# TopLevelDesign.net
KiCad netlist of a schematic drawn in Altium Designer
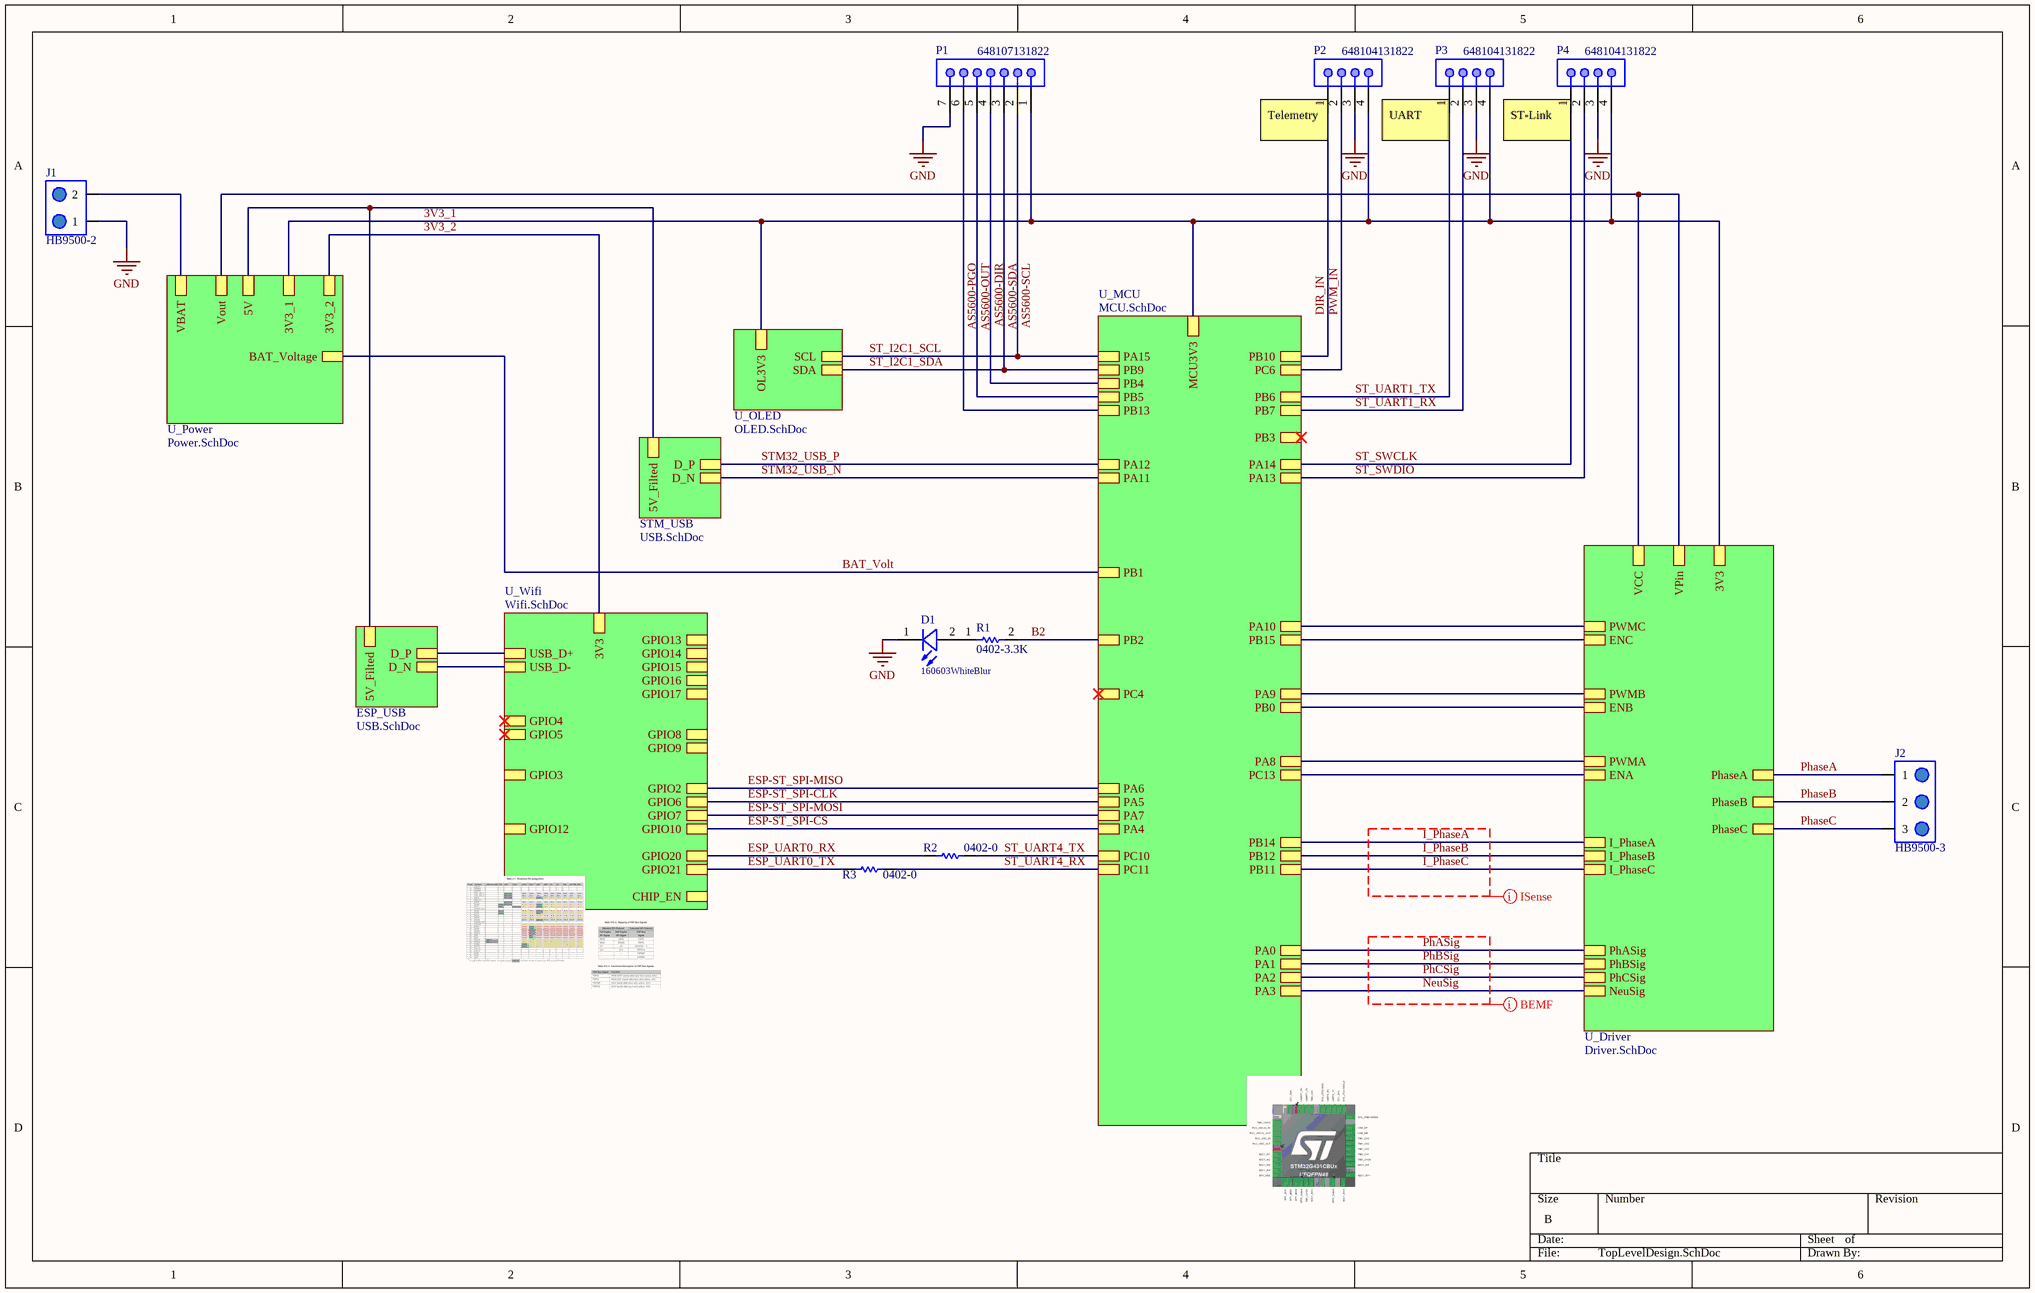
[diagram p0: TopLevelDesign.SchDoc]

(export (version "E")
  (design (tool "Eeschema 10.0.6"))
  (components
    (comp (ref "D1")
      (value "160603WhiteBlur")
      (footprint "WL-SMCW_0603_H=0.7mm")
      (description "WL-SMCW SMT Mono-color Chip LED Blur, size 0603, White")
      (libsource (lib "Tin Tran") (part "160603WhiteClear"))
    )
    (comp (ref "J1")
      (value "HB9500-2")
      (footprint "HB9500-2")
      (description "High Power Terminal , 25A , 300V")
      (libsource (lib "Tin Tran") (part "HB9500-2"))
    )
    (comp (ref "J2")
      (value "HB9500-3")
      (footprint "HB9500-3")
      (description "High Power Terminal , 25A , 300V")
      (libsource (lib "Tin Tran") (part "HB9500-3"))
    )
    (comp (ref "P1")
      (value "648107131822")
      (footprint "648107131822")
      (description "WR-WTB SMT Male Horizontal Shrouded Header, pitch 1.5mm, 7p")
      (fields (field (name "PUBLISHER") "Wurth Elektronik"))
      (libsource (lib "Tin Tran") (part "679307124022"))
    )
    (comp (ref "P2")
      (value "648104131822")
      (footprint "648104131822")
      (description "WR-WTB SMT Male Horizontal Shrouded Header, pitch 1.5mm, 4p")
      (fields (field (name "PUBLISHER") "Wurth Elektronik"))
      (libsource (lib "Tin Tran") (part "679304124022"))
    )
    (comp (ref "P3")
      (value "648104131822")
      (footprint "648104131822")
      (description "WR-WTB SMT Male Horizontal Shrouded Header, pitch 1.5mm, 4p")
      (fields (field (name "PUBLISHER") "Wurth Elektronik"))
      (libsource (lib "Tin Tran") (part "679304124022"))
    )
    (comp (ref "P4")
      (value "648104131822")
      (footprint "648104131822")
      (description "WR-WTB SMT Male Horizontal Shrouded Header, pitch 1.5mm, 4p")
      (fields (field (name "PUBLISHER") "Wurth Elektronik"))
      (libsource (lib "Tin Tran") (part "679304124022"))
    )
    (comp (ref "R1")
      (value "0402-3.3K")
      (footprint "R-0402-10K")
      (description "RES 0402 3.3K")
      (libsource (lib "") (part "0402_1"))
    )
    (comp (ref "R2")
      (value "0402-0")
      (footprint "R-0402-1K")
      (description "0402Resistor 0 Ohm")
      (libsource (lib "Tin Tran") (part "0402"))
    )
    (comp (ref "R3")
      (value "0402-0")
      (footprint "R-0402-1K")
      (description "0402Resistor 0 Ohm")
      (libsource (lib "Tin Tran") (part "0402"))
    )
  )
  (nets
    (net (code "1") (name "/3V3_1") (class "Default")
      (node (ref "P1") (pin "1") (pinfunction "1_1") (pintype "passive"))
      (node (ref "P2") (pin "4") (pinfunction "4_4") (pintype "passive"))
      (node (ref "P3") (pin "4") (pinfunction "4_4") (pintype "passive"))
      (node (ref "P4") (pin "4") (pinfunction "4_4") (pintype "passive"))
    )
    (net (code "4") (name "/AS5600-DIR") (class "Default")
      (node (ref "P1") (pin "4") (pinfunction "4_4") (pintype "passive"))
    )
    (net (code "5") (name "/AS5600-OUT") (class "Default")
      (node (ref "P1") (pin "5") (pinfunction "5_5") (pintype "passive"))
    )
    (net (code "6") (name "/AS5600-PGO") (class "Default")
      (node (ref "P1") (pin "6") (pinfunction "6_6") (pintype "passive"))
    )
    (net (code "7") (name "/AS5600-SCL") (class "Default")
      (node (ref "P1") (pin "2") (pinfunction "2_2") (pintype "passive"))
    )
    (net (code "8") (name "/AS5600-SDA") (class "Default")
      (node (ref "P1") (pin "3") (pinfunction "3_3") (pintype "passive"))
    )
    (net (code "9") (name "/B2") (class "Default")
      (node (ref "R1") (pin "2") (pinfunction "2_2") (pintype "passive"))
    )
    (net (code "12") (name "/DIR_IN") (class "Default")
      (node (ref "P2") (pin "1") (pinfunction "1_1") (pintype "passive"))
    )
    (net (code "22") (name "/ESP_UART0_RX") (class "Default")
      (node (ref "R2") (pin "1") (pinfunction "1_1") (pintype "passive"))
    )
    (net (code "23") (name "/ESP_UART0_TX") (class "Default")
      (node (ref "R3") (pin "1") (pinfunction "1_1") (pintype "passive"))
    )
    (net (code "44") (name "/PWM_IN") (class "Default")
      (node (ref "P2") (pin "2") (pinfunction "2_2") (pintype "passive"))
    )
    (net (code "48") (name "/PhaseA") (class "Default")
      (node (ref "J2") (pin "1") (pinfunction "1_1") (pintype "passive"))
    )
    (net (code "49") (name "/PhaseB") (class "Default")
      (node (ref "J2") (pin "2") (pinfunction "2_2") (pintype "passive"))
    )
    (net (code "50") (name "/PhaseC") (class "Default")
      (node (ref "J2") (pin "3") (pinfunction "3_3") (pintype "passive"))
    )
    (net (code "53") (name "/ST_SWCLK") (class "Default")
      (node (ref "P4") (pin "1") (pinfunction "1_1") (pintype "passive"))
    )
    (net (code "54") (name "/ST_SWDIO") (class "Default")
      (node (ref "P4") (pin "2") (pinfunction "2_2") (pintype "passive"))
    )
    (net (code "55") (name "/ST_UART1_RX") (class "Default")
      (node (ref "P3") (pin "2") (pinfunction "2_2") (pintype "passive"))
    )
    (net (code "56") (name "/ST_UART1_TX") (class "Default")
      (node (ref "P3") (pin "1") (pinfunction "1_1") (pintype "passive"))
    )
    (net (code "57") (name "/ST_UART4_RX") (class "Default")
      (node (ref "R3") (pin "2") (pinfunction "2_2") (pintype "passive"))
    )
    (net (code "58") (name "/ST_UART4_TX") (class "Default")
      (node (ref "R2") (pin "2") (pinfunction "2_2") (pintype "passive"))
    )
    (net (code "59") (name "/VBAT") (class "Default")
      (node (ref "J1") (pin "2") (pinfunction "2_2") (pintype "passive"))
    )
    (net (code "61") (name "GND") (class "Default")
      (node (ref "D1") (pin "1") (pinfunction "K_1") (pintype "passive"))
      (node (ref "J1") (pin "1") (pinfunction "1_1") (pintype "passive"))
      (node (ref "P1") (pin "7") (pinfunction "7_7") (pintype "passive"))
      (node (ref "P2") (pin "3") (pinfunction "3_3") (pintype "passive"))
      (node (ref "P3") (pin "3") (pinfunction "3_3") (pintype "passive"))
      (node (ref "P4") (pin "3") (pinfunction "3_3") (pintype "passive"))
    )
    (net (code "62") (name "Net-(D1-A)") (class "Default")
      (node (ref "D1") (pin "2") (pinfunction "A_2") (pintype "passive"))
      (node (ref "R1") (pin "1") (pinfunction "1_1") (pintype "passive"))
    )
  )
)
